# clock.net
KiCad netlist of a schematic drawn in EAGLE
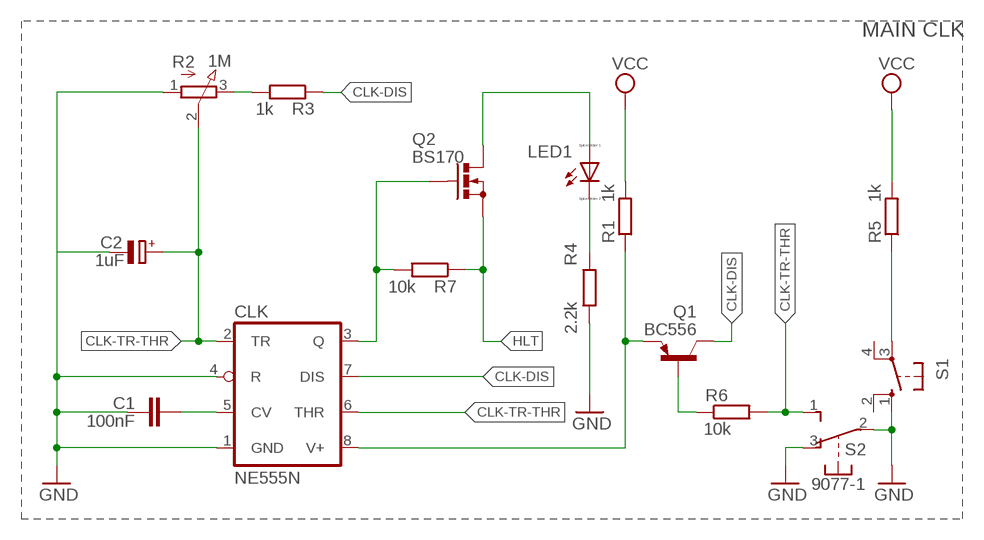
[diagram p0: schematic, sheet 1]

(export (version "E")
  (design (tool "Eeschema 10.0.6"))
  (components
    (comp (ref "C1")
      (value "100nF")
      (footprint "eagle-import:C025-050X050")
      (libsource (lib "eagle-import") (part "C-EU025-050X050"))
    )
    (comp (ref "C2")
      (value "1uF")
      (footprint "eagle-import:E2-5")
      (libsource (lib "eagle-import") (part "CPOL-EUE2-5"))
    )
    (comp (ref "CLK")
      (value "NE555N")
      (footprint "eagle-import:DIL08")
      (libsource (lib "eagle-import") (part "555NNE"))
    )
    (comp (ref "LED1")
      (value "LED_ELD260")
      (footprint "eagle-import:LED_LD260")
      (libsource (lib "eagle-import") (part "LED_ELD260"))
    )
    (comp (ref "Q1")
      (value "BC556")
      (footprint "eagle-import:TO92-EBC")
      (libsource (lib "eagle-import") (part "BC556"))
    )
    (comp (ref "Q2")
      (value "BS170")
      (footprint "eagle-import:SOT54E")
      (libsource (lib "eagle-import") (part "BS170"))
    )
    (comp (ref "R1")
      (value "1k")
      (footprint "eagle-import:0204_5")
      (libsource (lib "eagle-import") (part "R-EU_0204/5"))
    )
    (comp (ref "R2")
      (value "1M")
      (footprint "eagle-import:3RP_1610N")
      (libsource (lib "eagle-import") (part "3RP/1610N"))
    )
    (comp (ref "R3")
      (value "1k")
      (footprint "eagle-import:0204_5")
      (libsource (lib "eagle-import") (part "R-EU_0204/5"))
    )
    (comp (ref "R4")
      (value "2.2k")
      (footprint "eagle-import:0204_5")
      (libsource (lib "eagle-import") (part "R-EU_0204/5"))
    )
    (comp (ref "R5")
      (value "1k")
      (footprint "eagle-import:0204_5")
      (libsource (lib "eagle-import") (part "R-EU_0204/5"))
    )
    (comp (ref "R6")
      (value "10k")
      (footprint "eagle-import:0204_5")
      (libsource (lib "eagle-import") (part "R-EU_0204/5"))
    )
    (comp (ref "R7")
      (value "10k")
      (footprint "eagle-import:0204_5")
      (libsource (lib "eagle-import") (part "R-EU_0204/5"))
    )
    (comp (ref "S1")
      (value "10-XX")
      (footprint "eagle-import:B3F-10XX")
      (fields (field (name "MPN") "B3F-1000"))
      (libsource (lib "eagle-import") (part "10-XX"))
    )
    (comp (ref "S2")
      (value "9077-1")
      (footprint "eagle-import:9077-1")
      (libsource (lib "eagle-import") (part "9077-1"))
    )
  )
  (nets
    (net (code "1") (name "CLK-DIS") (class "Default")
      (node (ref "CLK") (pin "7") (pinfunction "DIS_7") (pintype "input"))
      (node (ref "Q1") (pin "C") (pinfunction "C_C") (pintype "passive"))
      (node (ref "R3") (pin "1") (pinfunction "1_1") (pintype "passive"))
    )
    (net (code "2") (name "CLK-TR-THR") (class "Default")
      (node (ref "C2") (pin "+") (pinfunction "+_+") (pintype "passive"))
      (node (ref "CLK") (pin "2") (pinfunction "TR_2") (pintype "input"))
      (node (ref "CLK") (pin "6") (pinfunction "THR_6") (pintype "input"))
      (node (ref "Q1") (pin "B") (pinfunction "B_B") (pintype "passive"))
      (node (ref "R2") (pin "2") (pinfunction "S_2") (pintype "passive"))
      (node (ref "R6") (pin "1") (pinfunction "1_1") (pintype "passive"))
      (node (ref "R6") (pin "2") (pinfunction "2_2") (pintype "passive"))
      (node (ref "S2") (pin "1") (pinfunction "S_1") (pintype "passive"))
    )
    (net (code "3") (name "GND") (class "Default")
      (node (ref "C1") (pin "1") (pinfunction "1_1") (pintype "passive"))
      (node (ref "C2") (pin "-") (pinfunction "-_-") (pintype "passive"))
      (node (ref "CLK") (pin "1") (pinfunction "GND_1") (pintype "power_in"))
      (node (ref "CLK") (pin "4") (pinfunction "R_4") (pintype "input"))
      (node (ref "R2") (pin "1") (pinfunction "A_1") (pintype "passive"))
      (node (ref "R4") (pin "2") (pinfunction "2_2") (pintype "passive"))
      (node (ref "S1") (pin "1") (pinfunction "S_1") (pintype "passive"))
      (node (ref "S2") (pin "2") (pinfunction "P_2") (pintype "passive"))
      (node (ref "S2") (pin "3") (pinfunction "O_3") (pintype "passive"))
    )
    (net (code "4") (name "HLT") (class "Default")
      (node (ref "Q2") (pin "S") (pinfunction "S_S") (pintype "passive"))
      (node (ref "R7") (pin "1") (pinfunction "1_1") (pintype "passive"))
    )
    (net (code "5") (name "Net-(CLK-CV)") (class "Default")
      (node (ref "C1") (pin "2") (pinfunction "2_2") (pintype "passive"))
      (node (ref "CLK") (pin "5") (pinfunction "CV_5") (pintype "input"))
    )
    (net (code "6") (name "Net-(CLK-Q)") (class "Default")
      (node (ref "CLK") (pin "3") (pinfunction "Q_3") (pintype "output"))
      (node (ref "Q2") (pin "G") (pinfunction "G_G") (pintype "passive"))
      (node (ref "R7") (pin "2") (pinfunction "2_2") (pintype "passive"))
    )
    (net (code "7") (name "Net-(CLK-V+)") (class "Default")
      (node (ref "CLK") (pin "8") (pinfunction "V+_8") (pintype "power_in"))
      (node (ref "Q1") (pin "E") (pinfunction "E_E") (pintype "passive"))
      (node (ref "R1") (pin "1") (pinfunction "1_1") (pintype "passive"))
    )
    (net (code "8") (name "Net-(LED1-C)") (class "Default")
      (node (ref "LED1") (pin "K") (pinfunction "C_K") (pintype "passive"))
      (node (ref "R4") (pin "1") (pinfunction "1_1") (pintype "passive"))
    )
    (net (code "9") (name "Net-(LED1-PadA)") (class "Default")
      (node (ref "LED1") (pin "A") (pinfunction "A_A") (pintype "passive"))
      (node (ref "Q2") (pin "D") (pinfunction "D_D") (pintype "passive"))
    )
    (net (code "10") (name "Net-(R2-E)") (class "Default")
      (node (ref "R2") (pin "3") (pinfunction "E_3") (pintype "passive"))
      (node (ref "R3") (pin "2") (pinfunction "2_2") (pintype "passive"))
    )
    (net (code "11") (name "Net-(S1-P)") (class "Default")
      (node (ref "R5") (pin "1") (pinfunction "1_1") (pintype "passive"))
      (node (ref "S1") (pin "3") (pinfunction "P_3") (pintype "passive"))
    )
    (net (code "12") (name "VCC") (class "Default")
      (node (ref "R1") (pin "2") (pinfunction "2_2") (pintype "passive"))
      (node (ref "R5") (pin "2") (pinfunction "2_2") (pintype "passive"))
    )
    (net (code "13") (name "unconnected-(S1-P1-Pad4)") (class "Default")
      (node (ref "S1") (pin "4") (pinfunction "P1_4") (pintype "passive"))
    )
    (net (code "14") (name "unconnected-(S1-S1-Pad2)") (class "Default")
      (node (ref "S1") (pin "2") (pinfunction "S1_2") (pintype "passive"))
    )
  )
)
